# drvinput5.net
KiCad netlist of a schematic drawn in Altium Designer
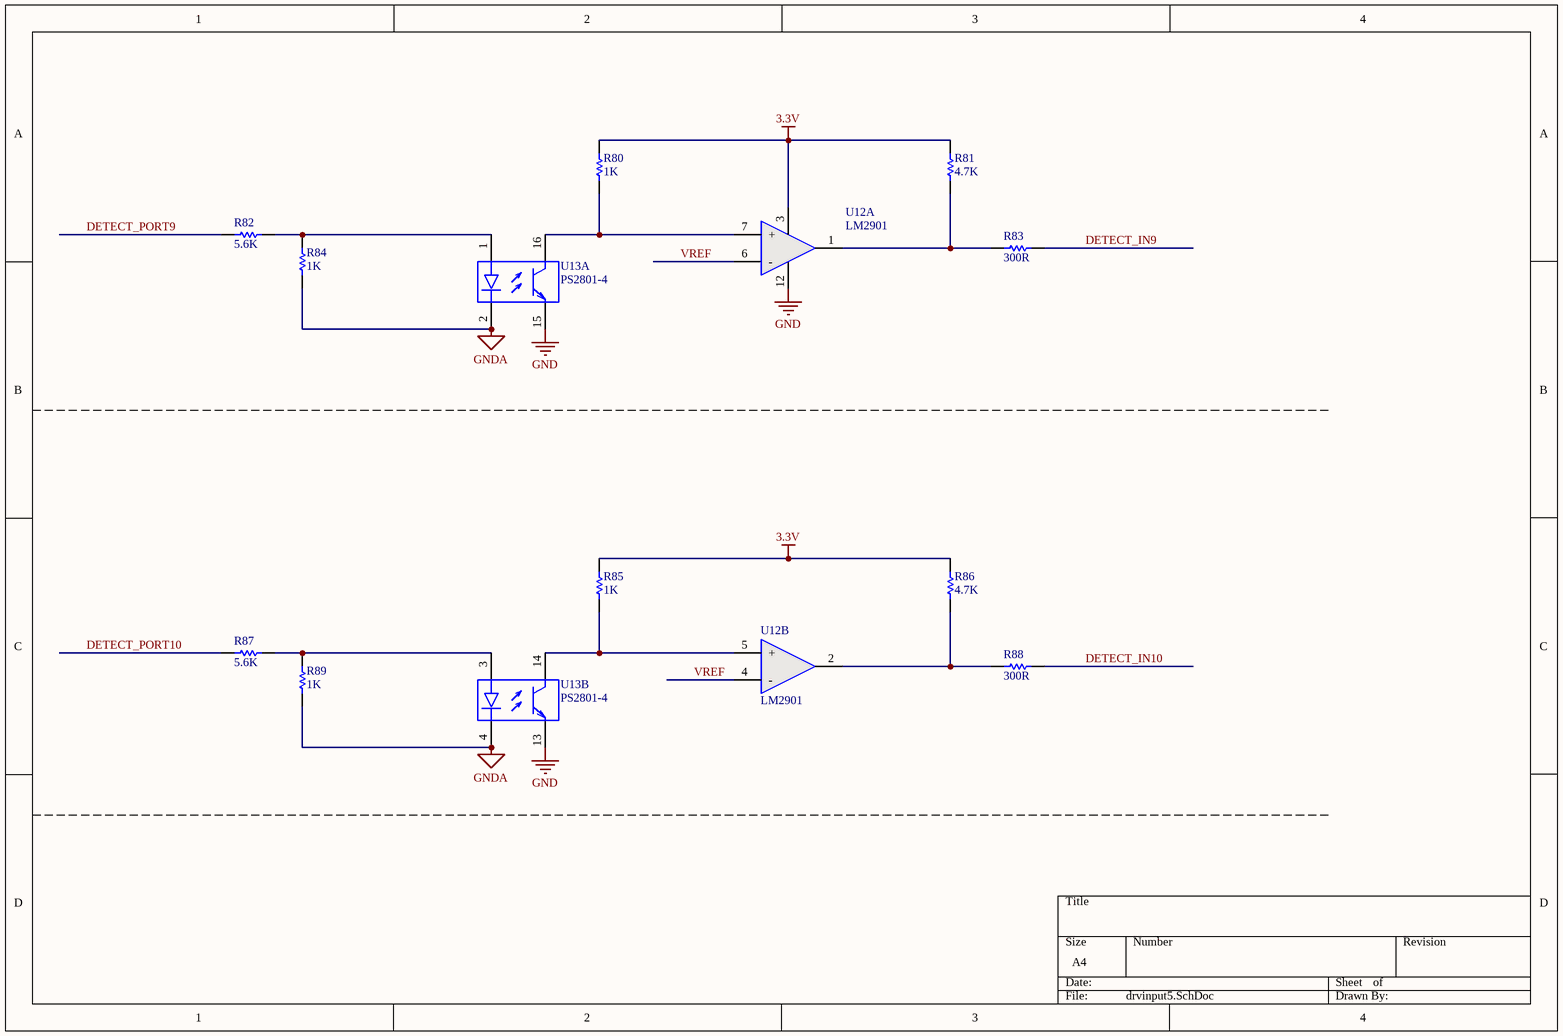
[diagram p0: drvinput5.SchDoc]

(export (version "E")
  (design (tool "Eeschema 10.0.6"))
  (components
    (comp (ref "R80")
      (value "1K")
      (footprint "RESC2012M")
      (description "Resistor")
      (fields (field (name "PUBLISHER") "Altium Limited"))
      (libsource (lib "Miscellaneous Devices") (part "Res1"))
    )
    (comp (ref "R81")
      (value "4.7K")
      (footprint "RESC2012M")
      (description "Resistor")
      (fields (field (name "PUBLISHER") "Altium Limited"))
      (libsource (lib "Miscellaneous Devices") (part "Res1"))
    )
    (comp (ref "R82")
      (value "5.6K")
      (footprint "RESC2012M")
      (description "Resistor")
      (fields (field (name "PUBLISHER") "Altium Limited"))
      (libsource (lib "Miscellaneous Devices") (part "Res1"))
    )
    (comp (ref "R83")
      (value "300R")
      (footprint "RESC2012M")
      (description "Resistor")
      (fields (field (name "PUBLISHER") "Altium Limited"))
      (libsource (lib "Miscellaneous Devices") (part "Res1"))
    )
    (comp (ref "R84")
      (value "1K")
      (footprint "RESC2012M")
      (description "Resistor")
      (fields (field (name "PUBLISHER") "Altium Limited"))
      (libsource (lib "Miscellaneous Devices") (part "Res1"))
    )
    (comp (ref "R85")
      (value "1K")
      (footprint "RESC2012M")
      (description "Resistor")
      (fields (field (name "PUBLISHER") "Altium Limited"))
      (libsource (lib "Miscellaneous Devices") (part "Res1"))
    )
    (comp (ref "R86")
      (value "4.7K")
      (footprint "RESC2012M")
      (description "Resistor")
      (fields (field (name "PUBLISHER") "Altium Limited"))
      (libsource (lib "Miscellaneous Devices") (part "Res1"))
    )
    (comp (ref "R87")
      (value "5.6K")
      (footprint "RESC2012M")
      (description "Resistor")
      (fields (field (name "PUBLISHER") "Altium Limited"))
      (libsource (lib "Miscellaneous Devices") (part "Res1"))
    )
    (comp (ref "R88")
      (value "300R")
      (footprint "RESC2012M")
      (description "Resistor")
      (fields (field (name "PUBLISHER") "Altium Limited"))
      (libsource (lib "Miscellaneous Devices") (part "Res1"))
    )
    (comp (ref "R89")
      (value "1K")
      (footprint "RESC2012M")
      (description "Resistor")
      (fields (field (name "PUBLISHER") "Altium Limited"))
      (libsource (lib "Miscellaneous Devices") (part "Res1"))
    )
    (comp (ref "U12")
      (value "LM2901")
      (footprint "SOIC-14AM")
      (description "4通道差分比较器芯片")
      (libsource (lib "UserSchDev") (part "LM2901"))
    )
    (comp (ref "U13")
      (value "PS2801-4")
      (footprint "SOIC16_N")
      (fields (field (name "PUBLISHER") "Altium Limited"))
      (libsource (lib "UserSchDev") (part "PS2801-4"))
    )
  )
  (nets
    (net (code "1") (name "/DETECT_IN9") (class "Default")
      (node (ref "R83") (pin "1") (pinfunction "1_1") (pintype "passive"))
    )
    (net (code "2") (name "/DETECT_IN10") (class "Default")
      (node (ref "R88") (pin "2") (pinfunction "2_2") (pintype "passive"))
    )
    (net (code "3") (name "/DETECT_PORT9") (class "Default")
      (node (ref "R82") (pin "2") (pinfunction "2_2") (pintype "passive"))
    )
    (net (code "4") (name "/DETECT_PORT10") (class "Default")
      (node (ref "R87") (pin "2") (pinfunction "2_2") (pintype "passive"))
    )
    (net (code "5") (name "/VREF") (class "Default")
      (node (ref "U12") (pin "4") (pinfunction "-_4") (pintype "passive"))
      (node (ref "U12") (pin "6") (pinfunction "-_6") (pintype "passive"))
    )
    (net (code "6") (name "3.3V") (class "Default")
      (node (ref "R80") (pin "1") (pinfunction "1_1") (pintype "passive"))
      (node (ref "R81") (pin "2") (pinfunction "2_2") (pintype "passive"))
      (node (ref "R85") (pin "1") (pinfunction "1_1") (pintype "passive"))
      (node (ref "R86") (pin "2") (pinfunction "2_2") (pintype "passive"))
      (node (ref "U12") (pin "3") (pinfunction "V+_3") (pintype "power_in"))
    )
    (net (code "7") (name "GND") (class "Default")
      (node (ref "U12") (pin "12") (pinfunction "V-_12") (pintype "power_in"))
      (node (ref "U13") (pin "13") (pinfunction "E_13") (pintype "passive"))
      (node (ref "U13") (pin "15") (pinfunction "E_15") (pintype "passive"))
    )
    (net (code "8") (name "GNDA") (class "Default")
      (node (ref "R84") (pin "1") (pinfunction "1_1") (pintype "passive"))
      (node (ref "R89") (pin "1") (pinfunction "1_1") (pintype "passive"))
      (node (ref "U13") (pin "2") (pinfunction "-_2") (pintype "passive"))
      (node (ref "U13") (pin "4") (pinfunction "-_4") (pintype "passive"))
    )
    (net (code "9") (name "Net-(U12A-+)") (class "Default")
      (node (ref "R80") (pin "2") (pinfunction "2_2") (pintype "passive"))
      (node (ref "U12") (pin "7") (pinfunction "+_7") (pintype "passive"))
      (node (ref "U13") (pin "16") (pinfunction "C_16") (pintype "passive"))
    )
    (net (code "10") (name "Net-(U12A-OUT)") (class "Default")
      (node (ref "R81") (pin "1") (pinfunction "1_1") (pintype "passive"))
      (node (ref "R83") (pin "2") (pinfunction "2_2") (pintype "passive"))
      (node (ref "U12") (pin "1") (pinfunction "OUT_1") (pintype "passive"))
    )
    (net (code "11") (name "Net-(U12B-+)") (class "Default")
      (node (ref "R85") (pin "2") (pinfunction "2_2") (pintype "passive"))
      (node (ref "U12") (pin "5") (pinfunction "+_5") (pintype "passive"))
      (node (ref "U13") (pin "14") (pinfunction "C_14") (pintype "passive"))
    )
    (net (code "12") (name "Net-(U12B-OUT)") (class "Default")
      (node (ref "R86") (pin "1") (pinfunction "1_1") (pintype "passive"))
      (node (ref "R88") (pin "1") (pinfunction "1_1") (pintype "passive"))
      (node (ref "U12") (pin "2") (pinfunction "OUT_2") (pintype "passive"))
    )
    (net (code "13") (name "Net-(U13A-+)") (class "Default")
      (node (ref "R82") (pin "1") (pinfunction "1_1") (pintype "passive"))
      (node (ref "R84") (pin "2") (pinfunction "2_2") (pintype "passive"))
      (node (ref "U13") (pin "1") (pinfunction "+_1") (pintype "passive"))
    )
    (net (code "14") (name "Net-(U13B-+)") (class "Default")
      (node (ref "R87") (pin "1") (pinfunction "1_1") (pintype "passive"))
      (node (ref "R89") (pin "2") (pinfunction "2_2") (pintype "passive"))
      (node (ref "U13") (pin "3") (pinfunction "+_3") (pintype "passive"))
    )
  )
)
